# Sensors.net
KiCad netlist of a schematic drawn in Altium Designer
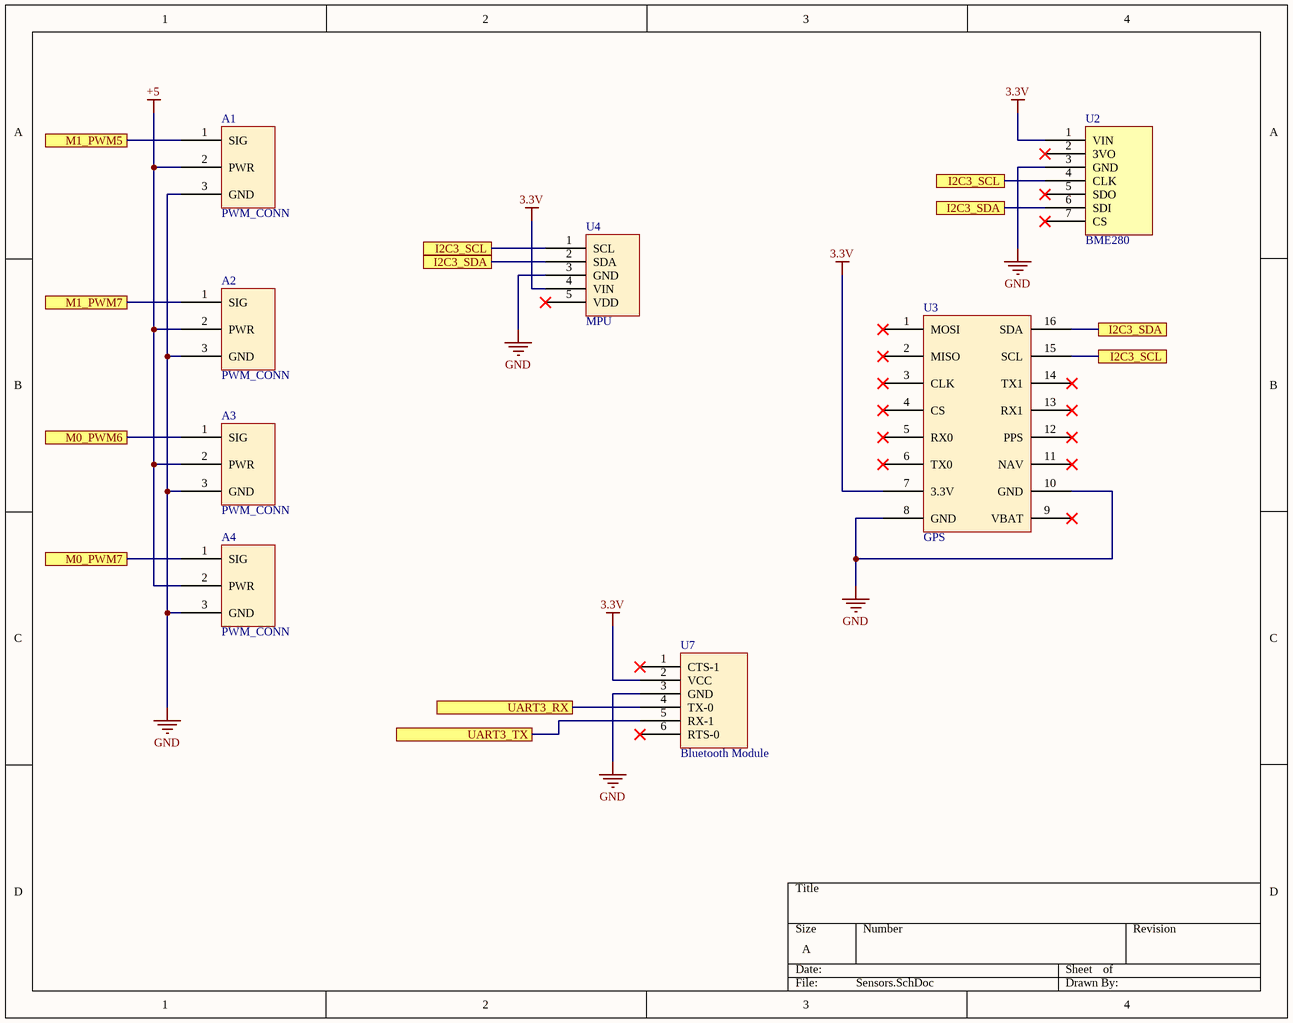
[diagram p0: Sensors.SchDoc]

(export (version "E")
  (design (tool "Eeschema 10.0.6"))
  (components
    (comp (ref "A1")
      (value "PWM_CONN")
      (footprint "Dupont")
      (libsource (lib "Quadrotor_Lib") (part "PWM_CONN"))
    )
    (comp (ref "A2")
      (value "PWM_CONN")
      (footprint "Dupont")
      (libsource (lib "Quadrotor_Lib") (part "PWM_CONN"))
    )
    (comp (ref "A3")
      (value "PWM_CONN")
      (footprint "Dupont")
      (libsource (lib "Quadrotor_Lib") (part "PWM_CONN"))
    )
    (comp (ref "A4")
      (value "PWM_CONN")
      (footprint "Dupont")
      (libsource (lib "Quadrotor_Lib") (part "PWM_CONN"))
    )
    (comp (ref "U2") (value "BME280") (footprint "BME280") (libsource (lib "Quadrotor_Lib") (part "BME280")))
    (comp (ref "U3") (value "GPS") (footprint "GPS_FOOTPRINT") (libsource (lib "Quadrotor_Lib") (part "GPS")))
    (comp (ref "U4") (value "MPU") (footprint "MPU") (libsource (lib "Quadrotor_Lib") (part "MPU")))
    (comp (ref "U7")
      (value "Bluetooth Module")
      (footprint "Bluetooth")
      (libsource (lib "Quadrotor_Lib") (part "Bluetooth Module"))
    )
  )
  (nets
    (net (code "1") (name "+5") (class "Default")
      (node (ref "A1") (pin "2") (pinfunction "PWR_2") (pintype "passive"))
      (node (ref "A2") (pin "2") (pinfunction "PWR_2") (pintype "passive"))
      (node (ref "A3") (pin "2") (pinfunction "PWR_2") (pintype "passive"))
      (node (ref "A4") (pin "2") (pinfunction "PWR_2") (pintype "passive"))
    )
    (net (code "2") (name "/I2C3_SCL") (class "Default")
      (node (ref "U2") (pin "4") (pinfunction "CLK_4") (pintype "passive"))
      (node (ref "U3") (pin "15") (pinfunction "SCL_15") (pintype "passive"))
      (node (ref "U4") (pin "1") (pinfunction "SCL_1") (pintype "passive"))
    )
    (net (code "3") (name "/I2C3_SDA") (class "Default")
      (node (ref "U2") (pin "6") (pinfunction "SDI_6") (pintype "passive"))
      (node (ref "U3") (pin "16") (pinfunction "SDA_16") (pintype "passive"))
      (node (ref "U4") (pin "2") (pinfunction "SDA_2") (pintype "passive"))
    )
    (net (code "4") (name "/M0_PWM6") (class "Default")
      (node (ref "A3") (pin "1") (pinfunction "SIG_1") (pintype "passive"))
    )
    (net (code "5") (name "/M0_PWM7") (class "Default")
      (node (ref "A4") (pin "1") (pinfunction "SIG_1") (pintype "passive"))
    )
    (net (code "6") (name "/M1_PWM5") (class "Default")
      (node (ref "A1") (pin "1") (pinfunction "SIG_1") (pintype "passive"))
    )
    (net (code "7") (name "/M1_PWM7") (class "Default")
      (node (ref "A2") (pin "1") (pinfunction "SIG_1") (pintype "passive"))
    )
    (net (code "8") (name "/UART3_RX") (class "Default")
      (node (ref "U7") (pin "4") (pinfunction "TX-0_4") (pintype "passive"))
    )
    (net (code "9") (name "/UART3_TX") (class "Default")
      (node (ref "U7") (pin "5") (pinfunction "RX-1_5") (pintype "passive"))
    )
    (net (code "10") (name "3.3V") (class "Default")
      (node (ref "U2") (pin "1") (pinfunction "VIN_1") (pintype "passive"))
      (node (ref "U3") (pin "7") (pinfunction "3.3V_7") (pintype "passive"))
      (node (ref "U4") (pin "4") (pinfunction "VIN_4") (pintype "passive"))
      (node (ref "U7") (pin "2") (pinfunction "VCC_2") (pintype "passive"))
    )
    (net (code "11") (name "GND") (class "Default")
      (node (ref "A1") (pin "3") (pinfunction "GND_3") (pintype "passive"))
      (node (ref "A2") (pin "3") (pinfunction "GND_3") (pintype "passive"))
      (node (ref "A3") (pin "3") (pinfunction "GND_3") (pintype "passive"))
      (node (ref "A4") (pin "3") (pinfunction "GND_3") (pintype "passive"))
      (node (ref "U2") (pin "3") (pinfunction "GND_3") (pintype "passive"))
      (node (ref "U3") (pin "10") (pinfunction "GND_10") (pintype "passive"))
      (node (ref "U3") (pin "8") (pinfunction "GND_8") (pintype "passive"))
      (node (ref "U4") (pin "3") (pinfunction "GND_3") (pintype "passive"))
      (node (ref "U7") (pin "3") (pinfunction "GND_3") (pintype "passive"))
    )
    (net (code "12") (name "unconnected-(U2-3VO-Pad2)") (class "Default")
      (node (ref "U2") (pin "2") (pinfunction "3VO_2") (pintype "passive+no_connect"))
    )
    (net (code "13") (name "unconnected-(U2-CS-Pad7)") (class "Default")
      (node (ref "U2") (pin "7") (pinfunction "CS_7") (pintype "passive+no_connect"))
    )
    (net (code "14") (name "unconnected-(U2-SDO-Pad5)") (class "Default")
      (node (ref "U2") (pin "5") (pinfunction "SDO_5") (pintype "passive+no_connect"))
    )
    (net (code "15") (name "unconnected-(U3-CLK-Pad3)") (class "Default")
      (node (ref "U3") (pin "3") (pinfunction "CLK_3") (pintype "passive+no_connect"))
    )
    (net (code "16") (name "unconnected-(U3-CS-Pad4)") (class "Default")
      (node (ref "U3") (pin "4") (pinfunction "CS_4") (pintype "passive+no_connect"))
    )
    (net (code "17") (name "unconnected-(U3-MISO-Pad2)") (class "Default")
      (node (ref "U3") (pin "2") (pinfunction "MISO_2") (pintype "passive+no_connect"))
    )
    (net (code "18") (name "unconnected-(U3-MOSI-Pad1)") (class "Default")
      (node (ref "U3") (pin "1") (pinfunction "MOSI_1") (pintype "passive+no_connect"))
    )
    (net (code "19") (name "unconnected-(U3-NAV-Pad11)") (class "Default")
      (node (ref "U3") (pin "11") (pinfunction "NAV_11") (pintype "passive+no_connect"))
    )
    (net (code "20") (name "unconnected-(U3-PPS-Pad12)") (class "Default")
      (node (ref "U3") (pin "12") (pinfunction "PPS_12") (pintype "passive+no_connect"))
    )
    (net (code "21") (name "unconnected-(U3-RX0-Pad5)") (class "Default")
      (node (ref "U3") (pin "5") (pinfunction "RX0_5") (pintype "passive+no_connect"))
    )
    (net (code "22") (name "unconnected-(U3-RX1-Pad13)") (class "Default")
      (node (ref "U3") (pin "13") (pinfunction "RX1_13") (pintype "passive+no_connect"))
    )
    (net (code "23") (name "unconnected-(U3-TX0-Pad6)") (class "Default")
      (node (ref "U3") (pin "6") (pinfunction "TX0_6") (pintype "passive+no_connect"))
    )
    (net (code "24") (name "unconnected-(U3-TX1-Pad14)") (class "Default")
      (node (ref "U3") (pin "14") (pinfunction "TX1_14") (pintype "passive+no_connect"))
    )
    (net (code "25") (name "unconnected-(U3-VBAT-Pad9)") (class "Default")
      (node (ref "U3") (pin "9") (pinfunction "VBAT_9") (pintype "passive+no_connect"))
    )
    (net (code "26") (name "unconnected-(U4-VDD-Pad5)") (class "Default")
      (node (ref "U4") (pin "5") (pinfunction "VDD_5") (pintype "passive+no_connect"))
    )
    (net (code "27") (name "unconnected-(U7-CTS-1-Pad1)") (class "Default")
      (node (ref "U7") (pin "1") (pinfunction "CTS-1_1") (pintype "passive+no_connect"))
    )
    (net (code "28") (name "unconnected-(U7-RTS-0-Pad6)") (class "Default")
      (node (ref "U7") (pin "6") (pinfunction "RTS-0_6") (pintype "passive+no_connect"))
    )
  )
)
